# Sheet1.net
KiCad netlist of a schematic drawn in Altium Designer
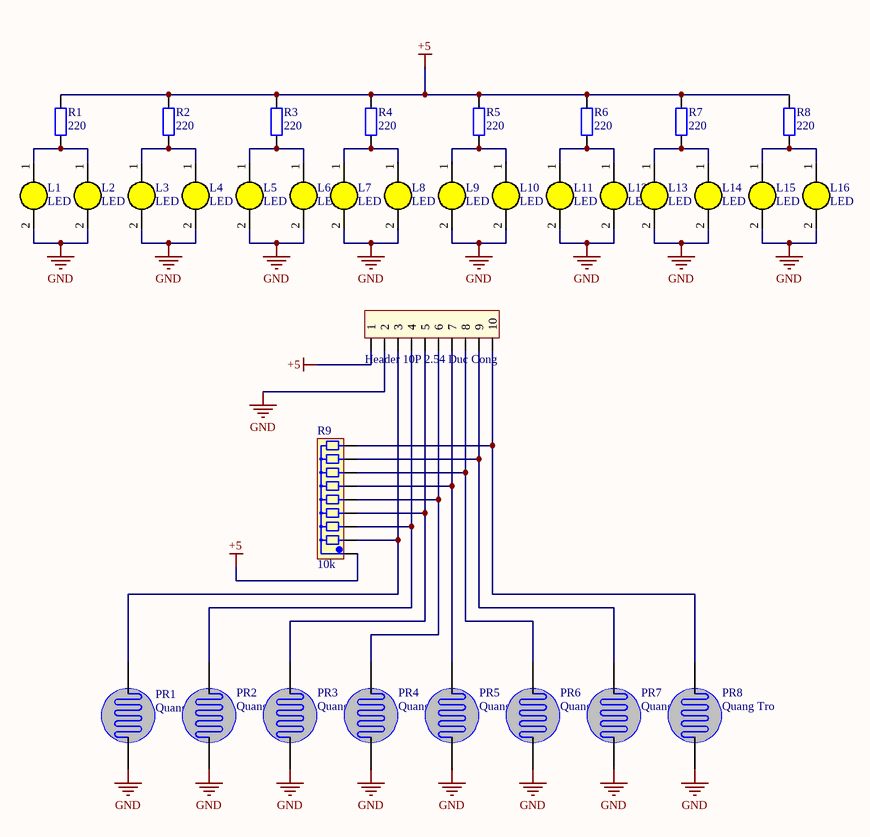
[diagram p0: Sheet1.SchDoc]

(export (version "E")
  (design (tool "Eeschema 10.0.6"))
  (components
    (comp (ref "H1")
      (value "Header 10P 2.54 Duc Cong")
      (footprint "Header 10P DC 2.54")
      (description "Cắm")
      (libsource (lib "Header") (part "Header 10P 2.54 Duc Cong"))
    )
    (comp (ref "L1")
      (value "LED")
      (footprint "LED-3MM-YELLOW")
      (description "Cắm")
      (libsource (lib "Led") (part "LED 3mm Vang"))
    )
    (comp (ref "L2")
      (value "LED")
      (footprint "LED-3MM-YELLOW")
      (description "Cắm")
      (libsource (lib "Led") (part "LED 3mm Vang"))
    )
    (comp (ref "L3")
      (value "LED")
      (footprint "LED-3MM-YELLOW")
      (description "Cắm")
      (libsource (lib "Led") (part "LED 3mm Vang"))
    )
    (comp (ref "L4")
      (value "LED")
      (footprint "LED-3MM-YELLOW")
      (description "Cắm")
      (libsource (lib "Led") (part "LED 3mm Vang"))
    )
    (comp (ref "L5")
      (value "LED")
      (footprint "LED-3MM-YELLOW")
      (description "Cắm")
      (libsource (lib "Led") (part "LED 3mm Vang"))
    )
    (comp (ref "L6")
      (value "LED")
      (footprint "LED-3MM-YELLOW")
      (description "Cắm")
      (libsource (lib "Led") (part "LED 3mm Vang"))
    )
    (comp (ref "L7")
      (value "LED")
      (footprint "LED-3MM-YELLOW")
      (description "Cắm")
      (libsource (lib "Led") (part "LED 3mm Vang"))
    )
    (comp (ref "L8")
      (value "LED")
      (footprint "LED-3MM-YELLOW")
      (description "Cắm")
      (libsource (lib "Led") (part "LED 3mm Vang"))
    )
    (comp (ref "L9")
      (value "LED")
      (footprint "LED-3MM-YELLOW")
      (description "Cắm")
      (libsource (lib "Led") (part "LED 3mm Vang"))
    )
    (comp (ref "L10")
      (value "LED")
      (footprint "LED-3MM-YELLOW")
      (description "Cắm")
      (libsource (lib "Led") (part "LED 3mm Vang"))
    )
    (comp (ref "L11")
      (value "LED")
      (footprint "LED-3MM-YELLOW")
      (description "Cắm")
      (libsource (lib "Led") (part "LED 3mm Vang"))
    )
    (comp (ref "L12")
      (value "LED")
      (footprint "LED-3MM-YELLOW")
      (description "Cắm")
      (libsource (lib "Led") (part "LED 3mm Vang"))
    )
    (comp (ref "L13")
      (value "LED")
      (footprint "LED-3MM-YELLOW")
      (description "Cắm")
      (libsource (lib "Led") (part "LED 3mm Vang"))
    )
    (comp (ref "L14")
      (value "LED")
      (footprint "LED-3MM-YELLOW")
      (description "Cắm")
      (libsource (lib "Led") (part "LED 3mm Vang"))
    )
    (comp (ref "L15")
      (value "LED")
      (footprint "LED-3MM-YELLOW")
      (description "Cắm")
      (libsource (lib "Led") (part "LED 3mm Vang"))
    )
    (comp (ref "L16")
      (value "LED")
      (footprint "LED-3MM-YELLOW")
      (description "Cắm")
      (libsource (lib "Led") (part "LED 3mm Vang"))
    )
    (comp (ref "PR1")
      (value "Quang Tro")
      (footprint "Quang Tro")
      (description "Photoresistor")
      (fields (field (name "CREATOR") "Bien Nguyen"))
      (libsource (lib "Component") (part "Quang Tro"))
    )
    (comp (ref "PR2")
      (value "Quang Tro")
      (footprint "Quang Tro")
      (description "Photoresistor")
      (fields (field (name "CREATOR") "Bien Nguyen"))
      (libsource (lib "Component") (part "Quang Tro"))
    )
    (comp (ref "PR3")
      (value "Quang Tro")
      (footprint "Quang Tro")
      (description "Photoresistor")
      (fields (field (name "CREATOR") "Bien Nguyen"))
      (libsource (lib "Component") (part "Quang Tro"))
    )
    (comp (ref "PR4")
      (value "Quang Tro")
      (footprint "Quang Tro")
      (description "Photoresistor")
      (fields (field (name "CREATOR") "Bien Nguyen"))
      (libsource (lib "Component") (part "Quang Tro"))
    )
    (comp (ref "PR5")
      (value "Quang Tro")
      (footprint "Quang Tro")
      (description "Photoresistor")
      (fields (field (name "CREATOR") "Bien Nguyen"))
      (libsource (lib "Component") (part "Quang Tro"))
    )
    (comp (ref "PR6")
      (value "Quang Tro")
      (footprint "Quang Tro")
      (description "Photoresistor")
      (fields (field (name "CREATOR") "Bien Nguyen"))
      (libsource (lib "Component") (part "Quang Tro"))
    )
    (comp (ref "PR7")
      (value "Quang Tro")
      (footprint "Quang Tro")
      (description "Photoresistor")
      (fields (field (name "CREATOR") "Bien Nguyen"))
      (libsource (lib "Component") (part "Quang Tro"))
    )
    (comp (ref "PR8")
      (value "Quang Tro")
      (footprint "Quang Tro")
      (description "Photoresistor")
      (fields (field (name "CREATOR") "Bien Nguyen"))
      (libsource (lib "Component") (part "Quang Tro"))
    )
    (comp (ref "R1")
      (value "220")
      (footprint "R1/4W")
      (description "Resistor 1/4W")
      (libsource (lib "syhaunguyen") (part "R1/4W"))
    )
    (comp (ref "R2")
      (value "220")
      (footprint "R1/4W")
      (description "Resistor 1/4W")
      (libsource (lib "syhaunguyen") (part "R1/4W"))
    )
    (comp (ref "R3")
      (value "220")
      (footprint "R1/4W")
      (description "Resistor 1/4W")
      (libsource (lib "syhaunguyen") (part "R1/4W"))
    )
    (comp (ref "R4")
      (value "220")
      (footprint "R1/4W")
      (description "Resistor 1/4W")
      (libsource (lib "syhaunguyen") (part "R1/4W"))
    )
    (comp (ref "R5")
      (value "220")
      (footprint "R1/4W")
      (description "Resistor 1/4W")
      (libsource (lib "syhaunguyen") (part "R1/4W"))
    )
    (comp (ref "R6")
      (value "220")
      (footprint "R1/4W")
      (description "Resistor 1/4W")
      (libsource (lib "syhaunguyen") (part "R1/4W"))
    )
    (comp (ref "R7")
      (value "220")
      (footprint "R1/4W")
      (description "Resistor 1/4W")
      (libsource (lib "syhaunguyen") (part "R1/4W"))
    )
    (comp (ref "R8")
      (value "220")
      (footprint "R1/4W")
      (description "Resistor 1/4W")
      (libsource (lib "syhaunguyen") (part "R1/4W"))
    )
    (comp (ref "R9")
      (value "10k")
      (footprint "tro bang a9")
      (description "Cắm")
      (libsource (lib "Resistor") (part "Tro Bang A9 10k"))
    )
  )
  (nets
    (net (code "1") (name "+5") (class "Default")
      (node (ref "H1") (pin "1") (pinfunction "1_1") (pintype "passive"))
      (node (ref "R1") (pin "2") (pinfunction "2_2") (pintype "passive"))
      (node (ref "R2") (pin "2") (pinfunction "2_2") (pintype "passive"))
      (node (ref "R3") (pin "2") (pinfunction "2_2") (pintype "passive"))
      (node (ref "R4") (pin "2") (pinfunction "2_2") (pintype "passive"))
      (node (ref "R5") (pin "2") (pinfunction "2_2") (pintype "passive"))
      (node (ref "R6") (pin "2") (pinfunction "2_2") (pintype "passive"))
      (node (ref "R7") (pin "2") (pinfunction "2_2") (pintype "passive"))
      (node (ref "R8") (pin "2") (pinfunction "2_2") (pintype "passive"))
      (node (ref "R9") (pin "1") (pinfunction "1_1") (pintype "passive"))
    )
    (net (code "2") (name "GND") (class "Default")
      (node (ref "H1") (pin "2") (pinfunction "2_2") (pintype "passive"))
      (node (ref "L1") (pin "2") (pinfunction "K_2") (pintype "passive"))
      (node (ref "L10") (pin "2") (pinfunction "K_2") (pintype "passive"))
      (node (ref "L11") (pin "2") (pinfunction "K_2") (pintype "passive"))
      (node (ref "L12") (pin "2") (pinfunction "K_2") (pintype "passive"))
      (node (ref "L13") (pin "2") (pinfunction "K_2") (pintype "passive"))
      (node (ref "L14") (pin "2") (pinfunction "K_2") (pintype "passive"))
      (node (ref "L15") (pin "2") (pinfunction "K_2") (pintype "passive"))
      (node (ref "L16") (pin "2") (pinfunction "K_2") (pintype "passive"))
      (node (ref "L2") (pin "2") (pinfunction "K_2") (pintype "passive"))
      (node (ref "L3") (pin "2") (pinfunction "K_2") (pintype "passive"))
      (node (ref "L4") (pin "2") (pinfunction "K_2") (pintype "passive"))
      (node (ref "L5") (pin "2") (pinfunction "K_2") (pintype "passive"))
      (node (ref "L6") (pin "2") (pinfunction "K_2") (pintype "passive"))
      (node (ref "L7") (pin "2") (pinfunction "K_2") (pintype "passive"))
      (node (ref "L8") (pin "2") (pinfunction "K_2") (pintype "passive"))
      (node (ref "L9") (pin "2") (pinfunction "K_2") (pintype "passive"))
      (node (ref "PR1") (pin "1") (pinfunction "1_1") (pintype "passive"))
      (node (ref "PR2") (pin "1") (pinfunction "1_1") (pintype "passive"))
      (node (ref "PR3") (pin "1") (pinfunction "1_1") (pintype "passive"))
      (node (ref "PR4") (pin "1") (pinfunction "1_1") (pintype "passive"))
      (node (ref "PR5") (pin "1") (pinfunction "1_1") (pintype "passive"))
      (node (ref "PR6") (pin "1") (pinfunction "1_1") (pintype "passive"))
      (node (ref "PR7") (pin "1") (pinfunction "1_1") (pintype "passive"))
      (node (ref "PR8") (pin "1") (pinfunction "1_1") (pintype "passive"))
    )
    (net (code "3") (name "Net-(H1-Pad3)") (class "Default")
      (node (ref "H1") (pin "3") (pinfunction "3_3") (pintype "passive"))
      (node (ref "PR1") (pin "2") (pinfunction "2_2") (pintype "passive"))
      (node (ref "R9") (pin "2") (pinfunction "2_2") (pintype "passive"))
    )
    (net (code "4") (name "Net-(H1-Pad4)") (class "Default")
      (node (ref "H1") (pin "4") (pinfunction "4_4") (pintype "passive"))
      (node (ref "PR2") (pin "2") (pinfunction "2_2") (pintype "passive"))
      (node (ref "R9") (pin "3") (pinfunction "3_3") (pintype "passive"))
    )
    (net (code "5") (name "Net-(H1-Pad5)") (class "Default")
      (node (ref "H1") (pin "5") (pinfunction "5_5") (pintype "passive"))
      (node (ref "PR3") (pin "2") (pinfunction "2_2") (pintype "passive"))
      (node (ref "R9") (pin "4") (pinfunction "4_4") (pintype "passive"))
    )
    (net (code "6") (name "Net-(H1-Pad6)") (class "Default")
      (node (ref "H1") (pin "6") (pinfunction "6_6") (pintype "passive"))
      (node (ref "PR4") (pin "2") (pinfunction "2_2") (pintype "passive"))
      (node (ref "R9") (pin "5") (pinfunction "5_5") (pintype "passive"))
    )
    (net (code "7") (name "Net-(H1-Pad7)") (class "Default")
      (node (ref "H1") (pin "7") (pinfunction "7_7") (pintype "passive"))
      (node (ref "PR5") (pin "2") (pinfunction "2_2") (pintype "passive"))
      (node (ref "R9") (pin "6") (pinfunction "6_6") (pintype "passive"))
    )
    (net (code "8") (name "Net-(H1-Pad8)") (class "Default")
      (node (ref "H1") (pin "8") (pinfunction "8_8") (pintype "passive"))
      (node (ref "PR6") (pin "2") (pinfunction "2_2") (pintype "passive"))
      (node (ref "R9") (pin "7") (pinfunction "7_7") (pintype "passive"))
    )
    (net (code "9") (name "Net-(H1-Pad9)") (class "Default")
      (node (ref "H1") (pin "9") (pinfunction "9_9") (pintype "passive"))
      (node (ref "PR7") (pin "2") (pinfunction "2_2") (pintype "passive"))
      (node (ref "R9") (pin "8") (pinfunction "8_8") (pintype "passive"))
    )
    (net (code "10") (name "Net-(H1-Pad10)") (class "Default")
      (node (ref "H1") (pin "10") (pinfunction "10_10") (pintype "passive"))
      (node (ref "PR8") (pin "2") (pinfunction "2_2") (pintype "passive"))
      (node (ref "R9") (pin "9") (pinfunction "9_9") (pintype "passive"))
    )
    (net (code "11") (name "Net-(L1-A)") (class "Default")
      (node (ref "L1") (pin "1") (pinfunction "A_1") (pintype "passive"))
      (node (ref "L2") (pin "1") (pinfunction "A_1") (pintype "passive"))
      (node (ref "R1") (pin "1") (pinfunction "1_1") (pintype "passive"))
    )
    (net (code "12") (name "Net-(L3-A)") (class "Default")
      (node (ref "L3") (pin "1") (pinfunction "A_1") (pintype "passive"))
      (node (ref "L4") (pin "1") (pinfunction "A_1") (pintype "passive"))
      (node (ref "R2") (pin "1") (pinfunction "1_1") (pintype "passive"))
    )
    (net (code "13") (name "Net-(L5-A)") (class "Default")
      (node (ref "L5") (pin "1") (pinfunction "A_1") (pintype "passive"))
      (node (ref "L6") (pin "1") (pinfunction "A_1") (pintype "passive"))
      (node (ref "R3") (pin "1") (pinfunction "1_1") (pintype "passive"))
    )
    (net (code "14") (name "Net-(L7-A)") (class "Default")
      (node (ref "L7") (pin "1") (pinfunction "A_1") (pintype "passive"))
      (node (ref "L8") (pin "1") (pinfunction "A_1") (pintype "passive"))
      (node (ref "R4") (pin "1") (pinfunction "1_1") (pintype "passive"))
    )
    (net (code "15") (name "Net-(L10-A)") (class "Default")
      (node (ref "L10") (pin "1") (pinfunction "A_1") (pintype "passive"))
      (node (ref "L9") (pin "1") (pinfunction "A_1") (pintype "passive"))
      (node (ref "R5") (pin "1") (pinfunction "1_1") (pintype "passive"))
    )
    (net (code "16") (name "Net-(L11-A)") (class "Default")
      (node (ref "L11") (pin "1") (pinfunction "A_1") (pintype "passive"))
      (node (ref "L12") (pin "1") (pinfunction "A_1") (pintype "passive"))
      (node (ref "R6") (pin "1") (pinfunction "1_1") (pintype "passive"))
    )
    (net (code "17") (name "Net-(L13-A)") (class "Default")
      (node (ref "L13") (pin "1") (pinfunction "A_1") (pintype "passive"))
      (node (ref "L14") (pin "1") (pinfunction "A_1") (pintype "passive"))
      (node (ref "R7") (pin "1") (pinfunction "1_1") (pintype "passive"))
    )
    (net (code "18") (name "Net-(L15-A)") (class "Default")
      (node (ref "L15") (pin "1") (pinfunction "A_1") (pintype "passive"))
      (node (ref "L16") (pin "1") (pinfunction "A_1") (pintype "passive"))
      (node (ref "R8") (pin "1") (pinfunction "1_1") (pintype "passive"))
    )
  )
)
